# module_ktemp.net
KiCad netlist of a schematic drawn in EAGLE
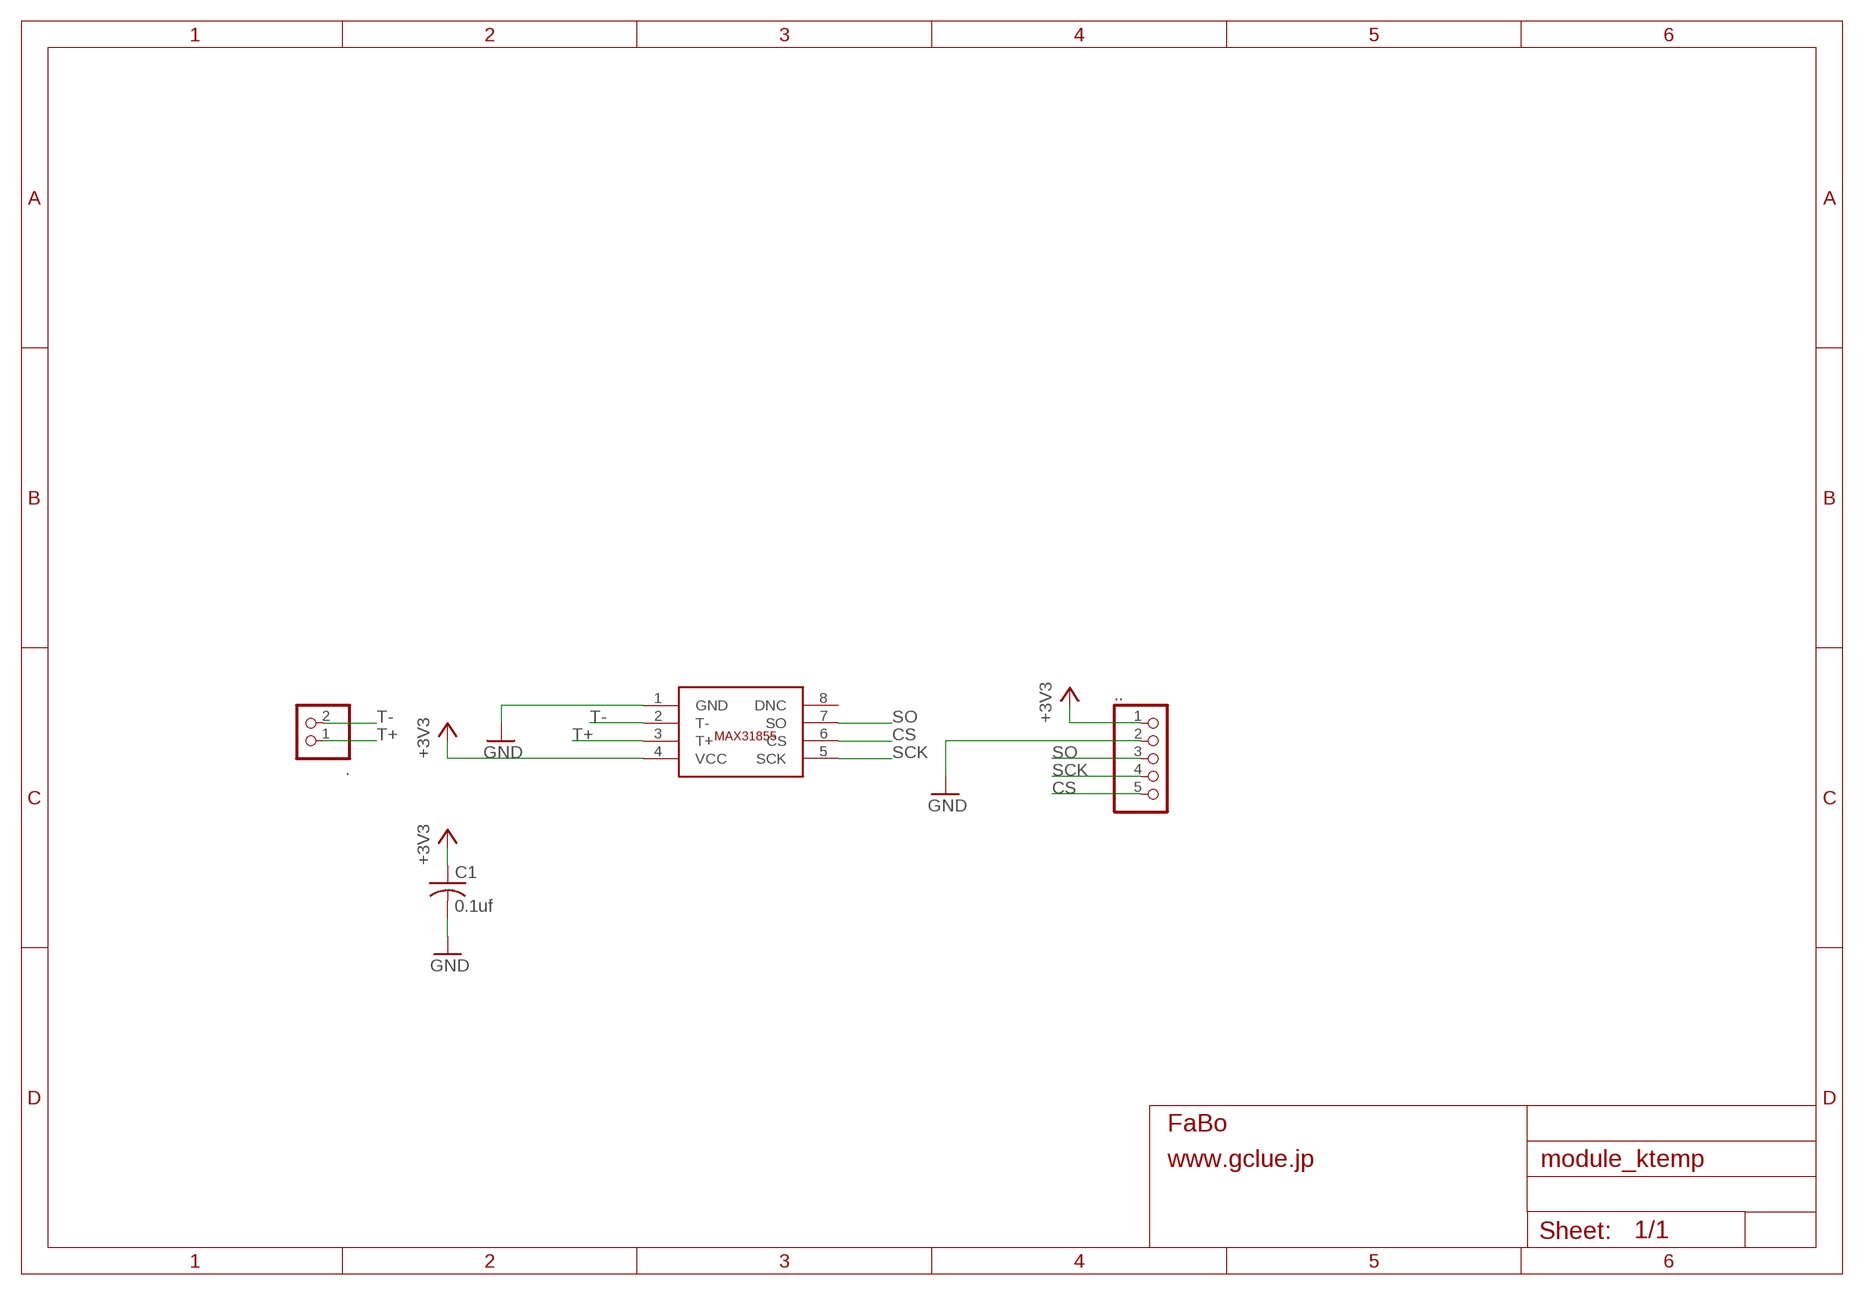
[diagram p0: schematic, sheet 1]

(export (version "E")
  (design (tool "Eeschema 10.0.6"))
  (components
    (comp (ref ".")
      (value "PINHD-1X2")
      (footprint "eagle-import:1X02")
      (libsource (lib "eagle-import") (part "PINHD-1X2"))
    )
    (comp (ref "..")
      (value "PINHD-1X5")
      (footprint "eagle-import:1X05")
      (libsource (lib "eagle-import") (part "PINHD-1X5"))
    )
    (comp (ref "C1")
      (value "0.1uf")
      (footprint "eagle-import:C0603")
      (libsource (lib "eagle-import") (part "C-USC0603"))
    )
    (comp (ref "U$2")
      (value "MAXIM-MAX31855")
      (footprint "eagle-import:MAXIM-MAX31855")
      (libsource (lib "eagle-import") (part "MAXIM-MAX31855"))
    )
  )
  (nets
    (net (code "1") (name "+3V3") (class "Default")
      (node (ref "..") (pin "1") (pinfunction "1_1") (pintype "passive"))
      (node (ref "C1") (pin "1") (pinfunction "1_1") (pintype "passive"))
      (node (ref "U$2") (pin "4") (pinfunction "VCC_4") (pintype "bidirectional"))
    )
    (net (code "2") (name "/CS") (class "Default")
      (node (ref "..") (pin "5") (pinfunction "5_5") (pintype "passive"))
      (node (ref "U$2") (pin "6") (pinfunction "CS_6") (pintype "bidirectional"))
    )
    (net (code "3") (name "/SCK") (class "Default")
      (node (ref "..") (pin "4") (pinfunction "4_4") (pintype "passive"))
      (node (ref "U$2") (pin "5") (pinfunction "SCK_5") (pintype "bidirectional"))
    )
    (net (code "4") (name "/SO") (class "Default")
      (node (ref "..") (pin "3") (pinfunction "3_3") (pintype "passive"))
      (node (ref "U$2") (pin "7") (pinfunction "SO_7") (pintype "bidirectional"))
    )
    (net (code "5") (name "/T+") (class "Default")
      (node (ref ".") (pin "1") (pinfunction "1_1") (pintype "passive"))
      (node (ref "U$2") (pin "3") (pinfunction "T+_3") (pintype "bidirectional"))
    )
    (net (code "6") (name "/T-") (class "Default")
      (node (ref ".") (pin "2") (pinfunction "2_2") (pintype "passive"))
      (node (ref "U$2") (pin "2") (pinfunction "T-_2") (pintype "bidirectional"))
    )
    (net (code "7") (name "GND") (class "Default")
      (node (ref "..") (pin "2") (pinfunction "2_2") (pintype "passive"))
      (node (ref "C1") (pin "2") (pinfunction "2_2") (pintype "passive"))
      (node (ref "U$2") (pin "1") (pinfunction "GND_1") (pintype "bidirectional"))
    )
    (net (code "8") (name "unconnected-(U$2-DNC-Pad8)") (class "Default")
      (node (ref "U$2") (pin "8") (pinfunction "DNC_8") (pintype "bidirectional"))
    )
  )
)
